# discharge-circuit.net
KiCad netlist of a schematic drawn in Altium Designer
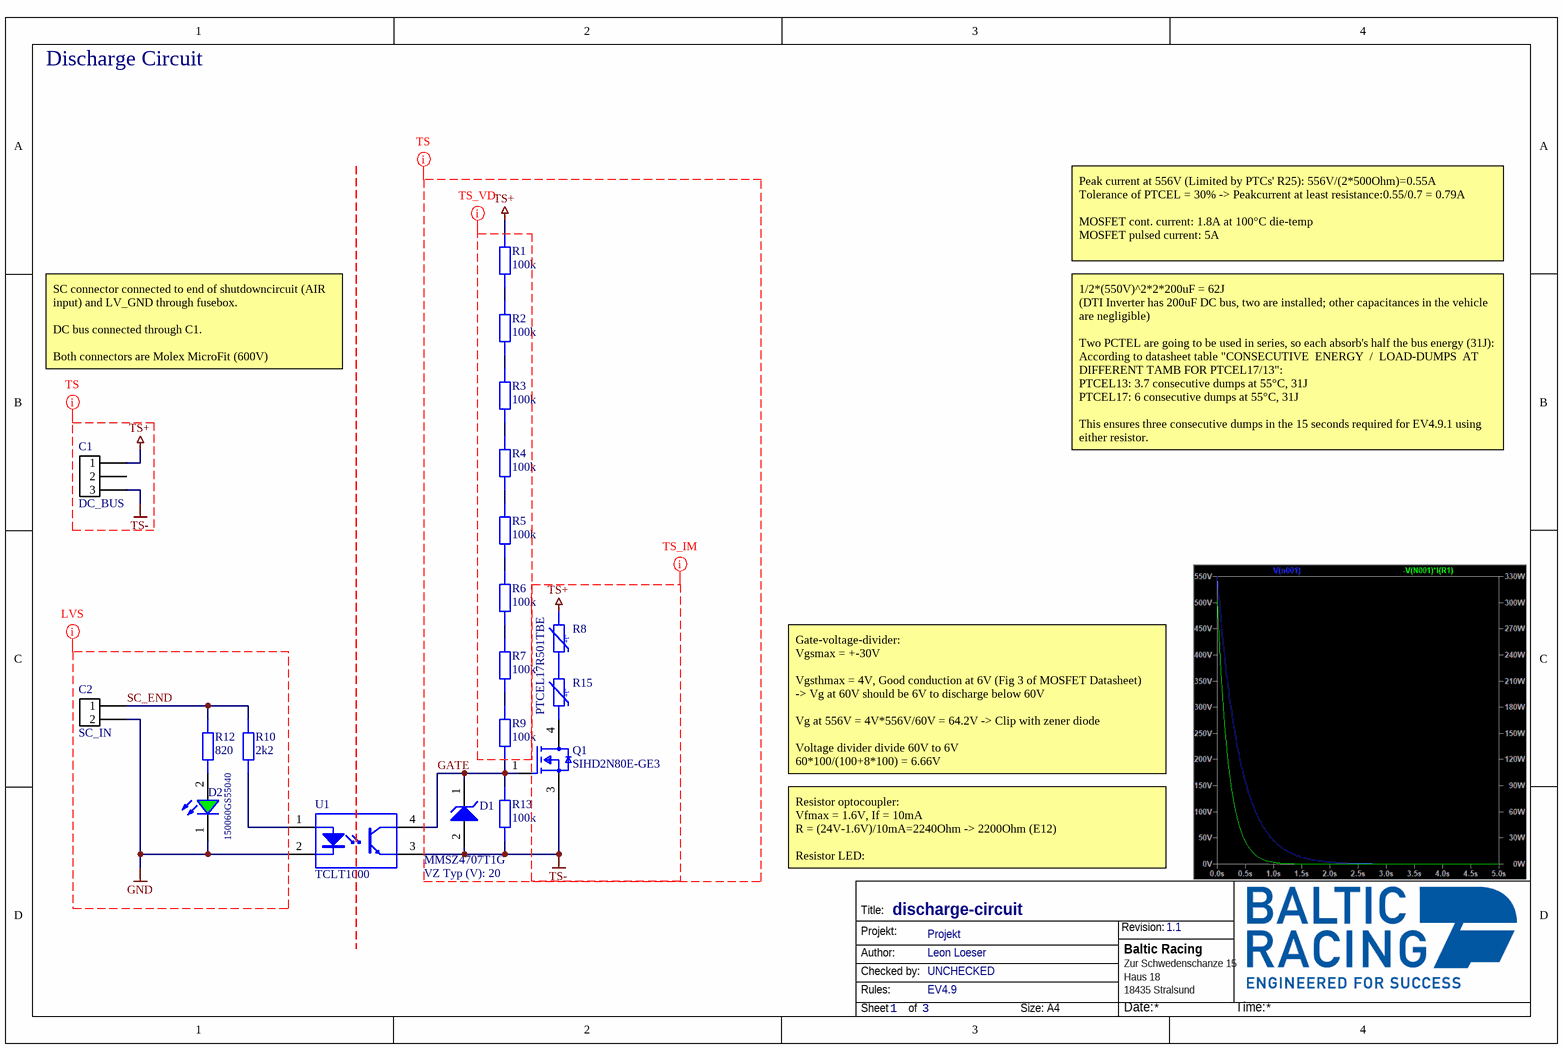
[diagram p0: discharge-circuit.SchDoc]

(export (version "E")
  (design (tool "Eeschema 10.0.6"))
  (components
    (comp (ref "C1")
      (value "DC_BUS")
      (footprint "43650-0309")
      (description "Molex Micro-Fit 3.0 3-Pin\r\n600V\r\n8.5A")
      (libsource (lib "Standardbauteile") (part "MicroFit3.0 3-Pin"))
    )
    (comp (ref "C2")
      (value "SC_IN")
      (footprint "43650-0200")
      (description "Molex Micro-Fit 3.0 2-Pin\r\n600V\r\n8.5A")
      (libsource (lib "Standardbauteile") (part "MicroFit3.0 2-Pin"))
    )
    (comp (ref "D1")
      (value "MMSZ4707T1G")
      (footprint "ONSC-SOD-123-2-425-04_V")
      (description "Zener Voltage Regulator, 500 mW, 2-Pin SOD-123, Pb-Free, Tape and Reel")
      (fields (field (name "MANUFACTURER") "On Semiconductor") (field (name "VZ TYP (V)") "20"))
      (libsource (lib "Altium Content Vault") (part "ONSC-K1A2-2"))
    )
    (comp (ref "D2")
      (value "150060GS55040")
      (footprint "WL-SMCW_0603_H=0.7")
      (description "SMT Mono-color Chip LED Waterclear WL-SMCW, size 0603, Green, 3.2 V, 140 deg, 430 mcd")
      (fields (field (name "PART NUMBER") "150060GS75000") (field (name "PUBLISHER") "Wurth Elektronik"))
      (libsource (lib "ALTIUM-WL-SMCW-rev18c") (part "150060GS75000"))
    )
    (comp (ref "Q1")
      (value "SIHD2N80E-GE3")
      (footprint "FP-T16-0236-MFG")
      (description "MOSFET N-CH 800V 2.8A DPAK")
      (fields
        (field (name "MANUFACTURER") "Vishay")
        (field (name "OCTOPART") "https://octopart.com/sihd2n80e-ge3-vishay-84840963")
      )
      (libsource (lib "Altium Content Vault") (part "86656c45bbbddc162aead764a772c09"))
    )
    (comp (ref "R1")
      (value "100k")
      (footprint "STACKPOLE CSR1206")
      (description "Resistor with multiple footprints")
      (fields (field (name "Comment") "SMD Resistor"))
      (libsource (lib "Standardbauteile") (part "SMD Resistor"))
    )
    (comp (ref "R2")
      (value "100k")
      (footprint "STACKPOLE CSR1206")
      (description "Resistor with multiple footprints")
      (fields (field (name "Comment") "SMD Resistor"))
      (libsource (lib "Standardbauteile") (part "SMD Resistor"))
    )
    (comp (ref "R3")
      (value "100k")
      (footprint "STACKPOLE CSR1206")
      (description "Resistor with multiple footprints")
      (fields (field (name "Comment") "SMD Resistor"))
      (libsource (lib "Standardbauteile") (part "SMD Resistor"))
    )
    (comp (ref "R4")
      (value "100k")
      (footprint "STACKPOLE CSR1206")
      (description "Resistor with multiple footprints")
      (fields (field (name "Comment") "SMD Resistor"))
      (libsource (lib "Standardbauteile") (part "SMD Resistor"))
    )
    (comp (ref "R5")
      (value "100k")
      (footprint "STACKPOLE CSR1206")
      (description "Resistor with multiple footprints")
      (fields (field (name "Comment") "SMD Resistor"))
      (libsource (lib "Standardbauteile") (part "SMD Resistor"))
    )
    (comp (ref "R6")
      (value "100k")
      (footprint "STACKPOLE CSR1206")
      (description "Resistor with multiple footprints")
      (fields (field (name "Comment") "SMD Resistor"))
      (libsource (lib "Standardbauteile") (part "SMD Resistor"))
    )
    (comp (ref "R7")
      (value "100k")
      (footprint "STACKPOLE CSR1206")
      (description "Resistor with multiple footprints")
      (fields (field (name "Comment") "SMD Resistor"))
      (libsource (lib "Standardbauteile") (part "SMD Resistor"))
    )
    (comp (ref "R8")
      (value "PTCEL17R501TBE")
      (footprint "PTCEL17")
      (description "PTCEL Series 1000 V 500 Ohm ±30 % Radial Inrush Current Limiter PTC Thermistor")
      (fields (field (name "MANUFACTURER") "Vishay BCcomponents") (field (name "TOLERANCE") "30%"))
      (libsource (lib "Leon") (part "PTCEL17R501TBE"))
    )
    (comp (ref "R9")
      (value "100k")
      (footprint "STACKPOLE CSR1206")
      (description "Resistor with multiple footprints")
      (fields (field (name "Comment") "SMD Resistor"))
      (libsource (lib "Standardbauteile") (part "SMD Resistor"))
    )
    (comp (ref "R10")
      (value "2k2")
      (footprint "STACKPOLE CSR0603")
      (description "Resistor with multiple footprints")
      (fields (field (name "Comment") "SMD Resistor"))
      (libsource (lib "Standardbauteile") (part "SMD Resistor"))
    )
    (comp (ref "R12")
      (value "820")
      (footprint "STACKPOLE CSR0603")
      (description "Resistor with multiple footprints")
      (fields (field (name "Comment") "SMD Resistor"))
      (libsource (lib "Standardbauteile") (part "SMD Resistor"))
    )
    (comp (ref "R13")
      (value "100k")
      (footprint "STACKPOLE CSR0603")
      (description "Resistor with multiple footprints")
      (fields (field (name "Comment") "SMD Resistor"))
      (libsource (lib "Standardbauteile") (part "SMD Resistor"))
    )
    (comp (ref "R15")
      (value "PTCEL17R501TBE")
      (footprint "PTCEL17")
      (description "PTCEL Series 1000 V 500 Ohm ±30 % Radial Inrush Current Limiter PTC Thermistor")
      (fields (field (name "MANUFACTURER") "Vishay BCcomponents") (field (name "TOLERANCE") "30%"))
      (libsource (lib "Leon") (part "PTCEL17R501TBE"))
    )
    (comp (ref "U1")
      (value "TCLT1000")
      (footprint "VISH-SOP4L-4_V")
      (fields (field (name "MANUFACTURER") "Vishay/Semiconductor"))
      (libsource (lib "Altium Content Vault") (part "OPTO-ACEC-4"))
    )
  )
  (nets
    (net (code "1") (name "/GATE") (class "Default")
      (node (ref "D1") (pin "1") (pinfunction "K_1") (pintype "passive"))
      (node (ref "Q1") (pin "1") (pinfunction "G_1") (pintype "passive"))
      (node (ref "R13") (pin "2") (pinfunction "2_2") (pintype "passive"))
      (node (ref "R9") (pin "1") (pinfunction "1_1") (pintype "passive"))
      (node (ref "U1") (pin "4") (pinfunction "C_4") (pintype "passive"))
    )
    (net (code "2") (name "/SC_END") (class "Default")
      (node (ref "C2") (pin "1") (pinfunction "1_1") (pintype "passive"))
      (node (ref "R10") (pin "1") (pinfunction "1_1") (pintype "passive"))
      (node (ref "R12") (pin "2") (pinfunction "2_2") (pintype "passive"))
    )
    (net (code "3") (name "GND") (class "Default")
      (node (ref "C2") (pin "2") (pinfunction "2_2") (pintype "passive"))
      (node (ref "D2") (pin "1") (pinfunction "K_1") (pintype "passive"))
      (node (ref "U1") (pin "2") (pinfunction "C_2") (pintype "passive"))
    )
    (net (code "4") (name "Net-(D2-A)") (class "Default")
      (node (ref "D2") (pin "2") (pinfunction "A_2") (pintype "passive"))
      (node (ref "R12") (pin "1") (pinfunction "1_1") (pintype "passive"))
    )
    (net (code "5") (name "Net-(Q1-D)") (class "Default")
      (node (ref "Q1") (pin "4") (pinfunction "D_4") (pintype "passive"))
      (node (ref "R15") (pin "2") (pinfunction "2_2") (pintype "passive"))
    )
    (net (code "6") (name "Net-(R1-Pad1)") (class "Default")
      (node (ref "R1") (pin "1") (pinfunction "1_1") (pintype "passive"))
      (node (ref "R2") (pin "2") (pinfunction "2_2") (pintype "passive"))
    )
    (net (code "7") (name "Net-(R2-Pad1)") (class "Default")
      (node (ref "R2") (pin "1") (pinfunction "1_1") (pintype "passive"))
      (node (ref "R3") (pin "2") (pinfunction "2_2") (pintype "passive"))
    )
    (net (code "8") (name "Net-(R3-Pad1)") (class "Default")
      (node (ref "R3") (pin "1") (pinfunction "1_1") (pintype "passive"))
      (node (ref "R4") (pin "2") (pinfunction "2_2") (pintype "passive"))
    )
    (net (code "9") (name "Net-(R4-Pad1)") (class "Default")
      (node (ref "R4") (pin "1") (pinfunction "1_1") (pintype "passive"))
      (node (ref "R5") (pin "2") (pinfunction "2_2") (pintype "passive"))
    )
    (net (code "10") (name "Net-(R5-Pad1)") (class "Default")
      (node (ref "R5") (pin "1") (pinfunction "1_1") (pintype "passive"))
      (node (ref "R6") (pin "2") (pinfunction "2_2") (pintype "passive"))
    )
    (net (code "11") (name "Net-(R6-Pad1)") (class "Default")
      (node (ref "R6") (pin "1") (pinfunction "1_1") (pintype "passive"))
      (node (ref "R7") (pin "2") (pinfunction "2_2") (pintype "passive"))
    )
    (net (code "12") (name "Net-(R7-Pad1)") (class "Default")
      (node (ref "R7") (pin "1") (pinfunction "1_1") (pintype "passive"))
      (node (ref "R9") (pin "2") (pinfunction "2_2") (pintype "passive"))
    )
    (net (code "13") (name "Net-(R15-Pad1)") (class "Default")
      (node (ref "R15") (pin "1") (pinfunction "1_1") (pintype "passive"))
      (node (ref "R8") (pin "2") (pinfunction "2_2") (pintype "passive"))
    )
    (net (code "14") (name "Net-(U1-A)") (class "Default")
      (node (ref "R10") (pin "2") (pinfunction "2_2") (pintype "passive"))
      (node (ref "U1") (pin "1") (pinfunction "A_1") (pintype "passive"))
    )
    (net (code "15") (name "TS+") (class "Default")
      (node (ref "C1") (pin "1") (pinfunction "1_1") (pintype "passive"))
      (node (ref "R1") (pin "2") (pinfunction "2_2") (pintype "passive"))
      (node (ref "R8") (pin "1") (pinfunction "1_1") (pintype "passive"))
    )
    (net (code "16") (name "TS-") (class "Default")
      (node (ref "C1") (pin "3") (pinfunction "3_3") (pintype "passive"))
      (node (ref "D1") (pin "2") (pinfunction "A_2") (pintype "passive"))
      (node (ref "Q1") (pin "3") (pinfunction "S_3") (pintype "passive"))
      (node (ref "R13") (pin "1") (pinfunction "1_1") (pintype "passive"))
      (node (ref "U1") (pin "3") (pinfunction "E_3") (pintype "passive"))
    )
    (net (code "17") (name "unconnected-(C1-Pad2)") (class "Default")
      (node (ref "C1") (pin "2") (pinfunction "2_2") (pintype "passive"))
    )
  )
)
